# ProPrj_USB_Hub_Port_PCB_2026-06-10.net
KiCad netlist of a schematic drawn in EasyEDA Pro
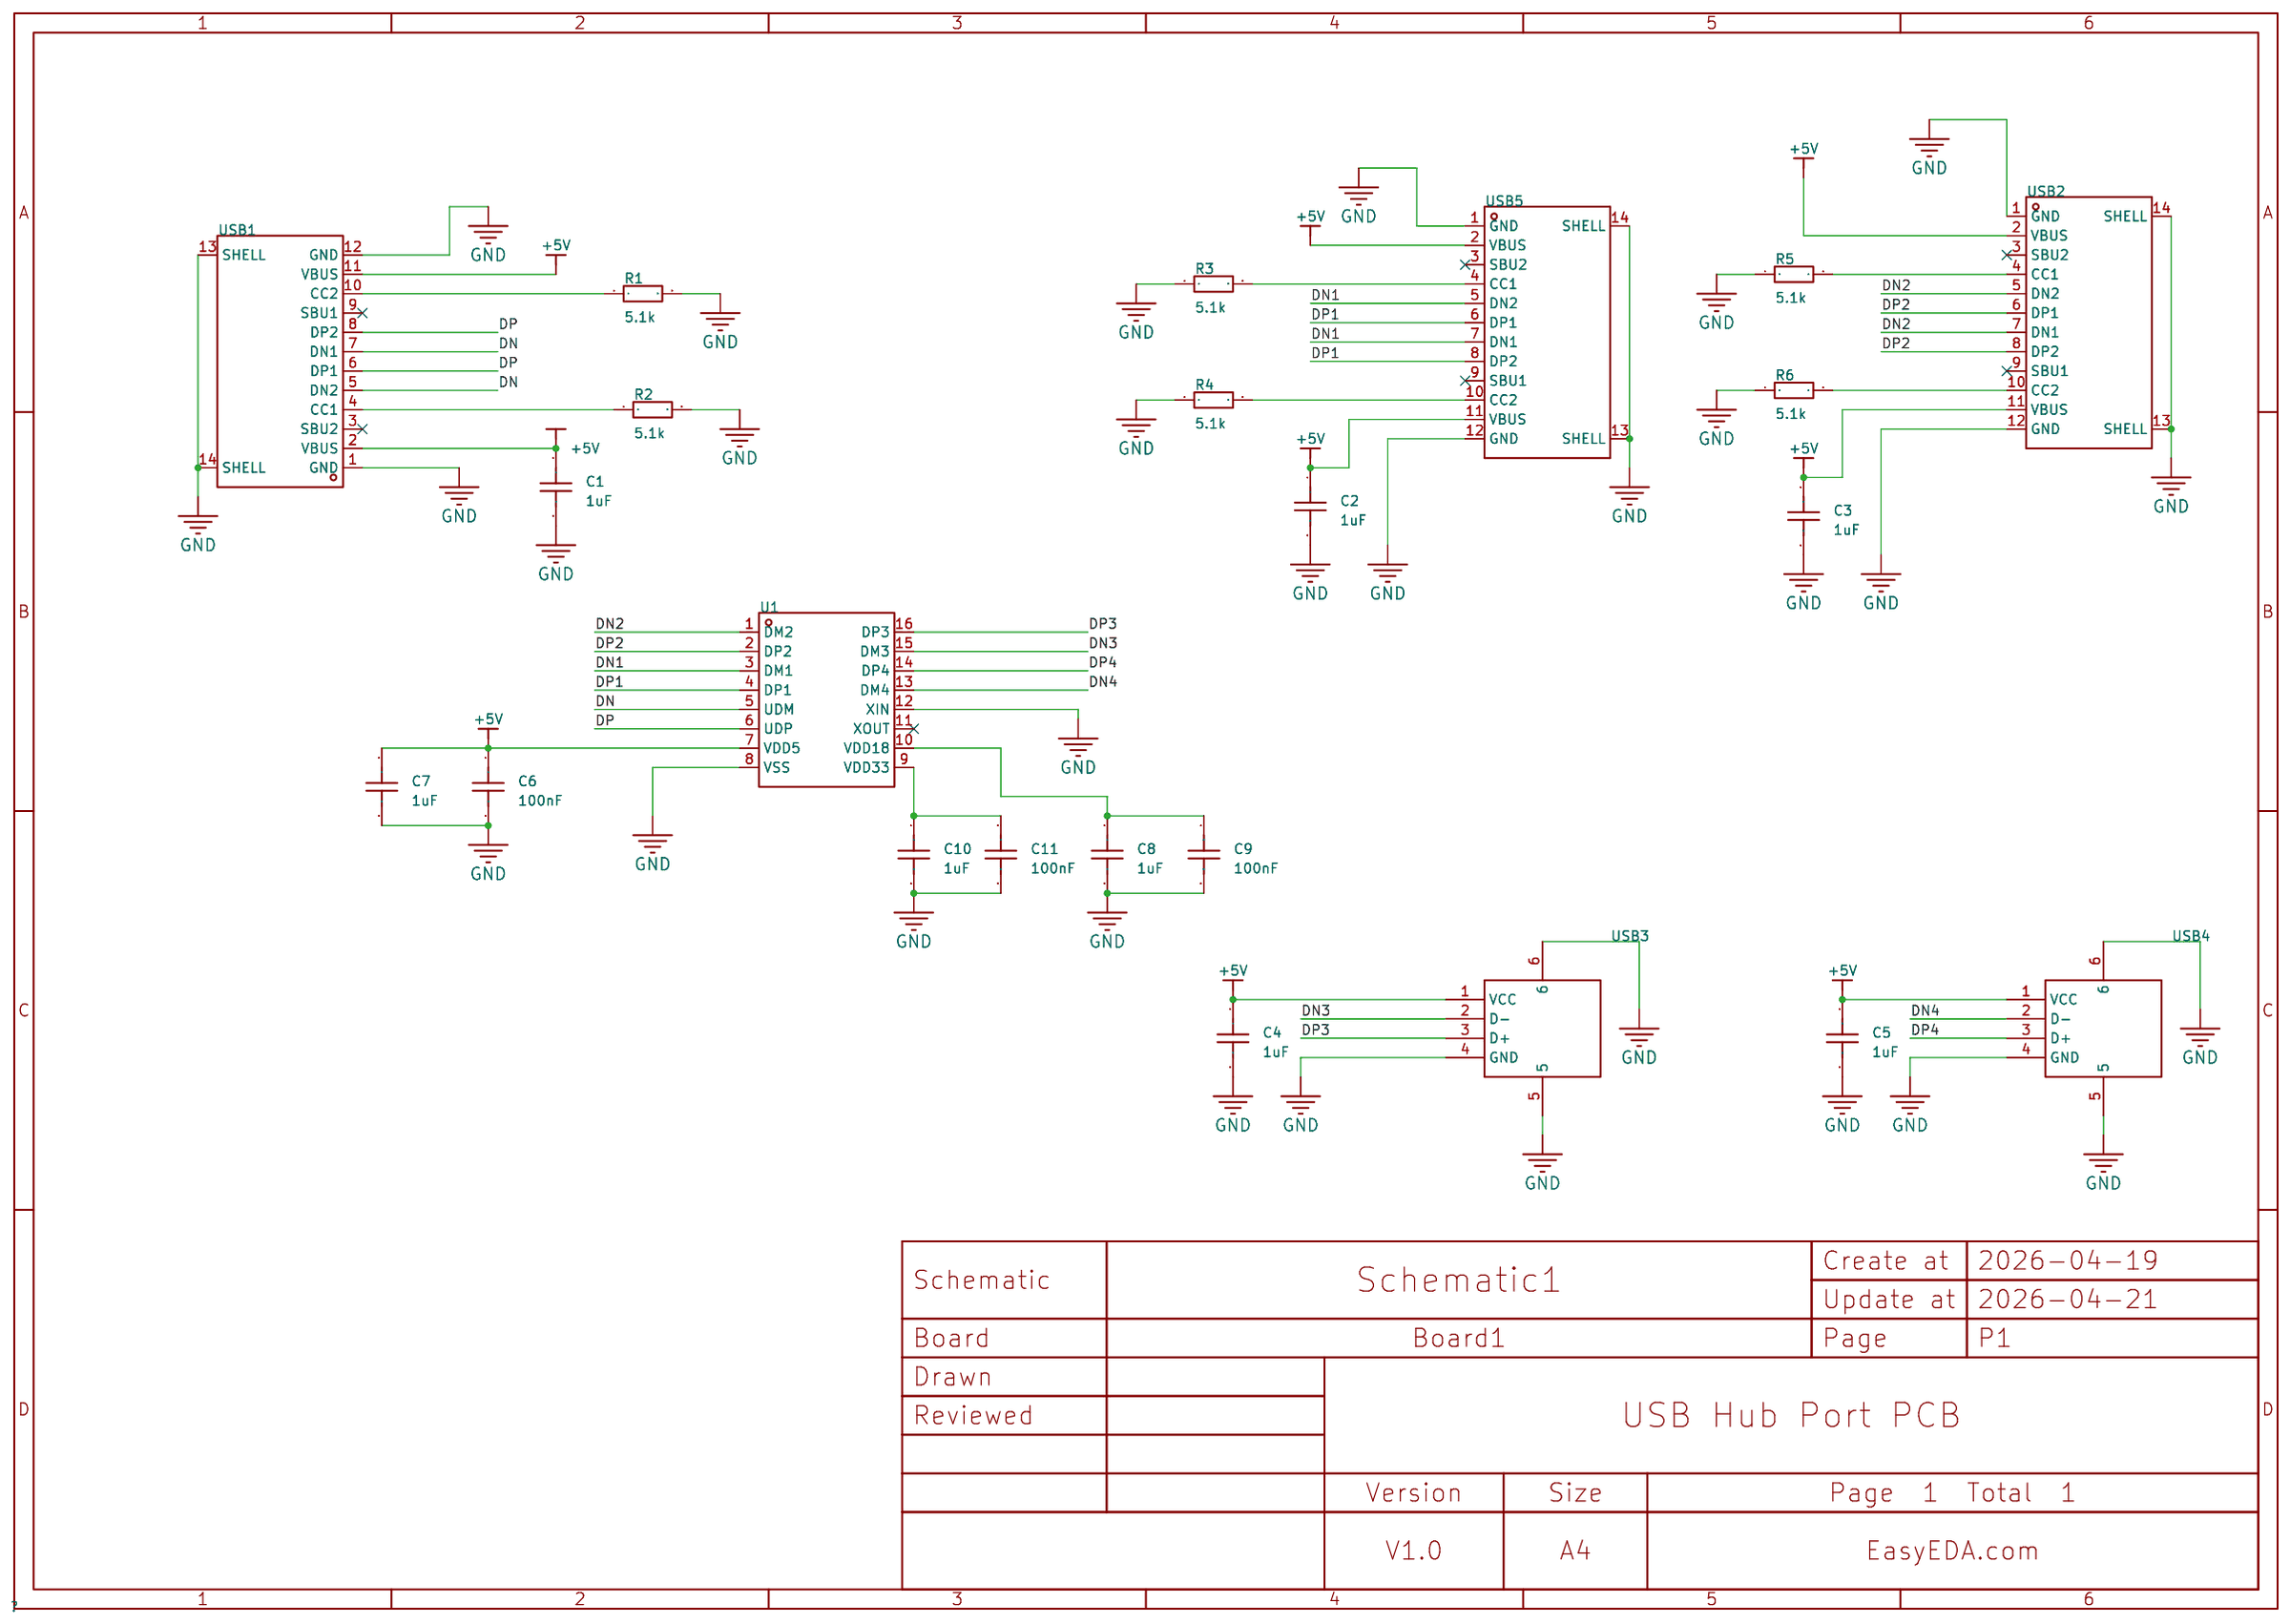
[diagram p0: schematic sheet]

(export (version "E")
  (design (tool "Eeschema 10.0.6"))
  (components
    (comp (ref "C1") (value "1uF") (footprint "easyedapro:C0603") (libsource (lib "easyedapro") (part "CAP")))
    (comp (ref "C2") (value "1uF") (footprint "easyedapro:C0603") (libsource (lib "easyedapro") (part "CAP")))
    (comp (ref "C3") (value "1uF") (footprint "easyedapro:C0603") (libsource (lib "easyedapro") (part "CAP")))
    (comp (ref "C4") (value "1uF") (footprint "easyedapro:C0603") (libsource (lib "easyedapro") (part "CAP")))
    (comp (ref "C5") (value "1uF") (footprint "easyedapro:C0603") (libsource (lib "easyedapro") (part "CAP")))
    (comp (ref "C6")
      (value "100nF")
      (footprint "easyedapro:C0603")
      (libsource (lib "easyedapro") (part "CAP"))
    )
    (comp (ref "C7") (value "1uF") (footprint "easyedapro:C0603") (libsource (lib "easyedapro") (part "CAP")))
    (comp (ref "C8") (value "1uF") (footprint "easyedapro:C0603") (libsource (lib "easyedapro") (part "CAP")))
    (comp (ref "C9")
      (value "100nF")
      (footprint "easyedapro:C0603")
      (libsource (lib "easyedapro") (part "CAP"))
    )
    (comp (ref "C10")
      (value "1uF")
      (footprint "easyedapro:C0603")
      (libsource (lib "easyedapro") (part "CAP"))
    )
    (comp (ref "C11")
      (value "100nF")
      (footprint "easyedapro:C0603")
      (libsource (lib "easyedapro") (part "CAP"))
    )
    (comp (ref "R1")
      (value "5.1k")
      (footprint "easyedapro:R0603")
      (libsource (lib "easyedapro") (part "Res"))
    )
    (comp (ref "R2")
      (value "5.1k")
      (footprint "easyedapro:R0603")
      (libsource (lib "easyedapro") (part "Res"))
    )
    (comp (ref "R3")
      (value "5.1k")
      (footprint "easyedapro:R0603")
      (libsource (lib "easyedapro") (part "Res"))
    )
    (comp (ref "R4")
      (value "5.1k")
      (footprint "easyedapro:R0603")
      (libsource (lib "easyedapro") (part "Res"))
    )
    (comp (ref "R5")
      (value "5.1k")
      (footprint "easyedapro:R0603")
      (libsource (lib "easyedapro") (part "Res"))
    )
    (comp (ref "R6")
      (value "5.1k")
      (footprint "easyedapro:R0603")
      (libsource (lib "easyedapro") (part "Res"))
    )
    (comp (ref "U1")
      (value "SL2.1s")
      (footprint "easyedapro:SSOP-16_L4.6-W2.6-P0.53-LS4.0-BL")
      (fields (field (name "Manufacturer") "CoreChips(和芯润德)"))
      (libsource (lib "easyedapro") (part "SL2.1S"))
    )
    (comp (ref "USB1")
      (value "TYPE-C 16PIN 2MD(073)")
      (footprint "easyedapro:USB-C-SMD_TYPE-C-6PIN-2MD-073")
      (fields (field (name "Manufacturer") "SHOU HAN(首韩)"))
      (libsource (lib "easyedapro") (part "TYPE-C 16PIN 2MD(073)"))
    )
    (comp (ref "USB2")
      (value "TYPE-C 16PIN 2MD(073)")
      (footprint "easyedapro:USB-C-SMD_TYPE-C-6PIN-2MD-073")
      (fields (field (name "Manufacturer") "SHOU HAN(首韩)"))
      (libsource (lib "easyedapro") (part "TYPE-C 16PIN 2MD(073)"))
    )
    (comp (ref "USB3")
      (value "10.0 QHHTZB6.3")
      (footprint "easyedapro:USB-A-TH_10.0QHHTZB6.3")
      (fields (field (name "Manufacturer") "SHOU HAN(首韩)"))
      (libsource (lib "easyedapro") (part "10.0 QHHTZB6.3"))
    )
    (comp (ref "USB4")
      (value "10.0 QHHTZB6.3")
      (footprint "easyedapro:USB-A-TH_10.0QHHTZB6.3")
      (fields (field (name "Manufacturer") "SHOU HAN(首韩)"))
      (libsource (lib "easyedapro") (part "10.0 QHHTZB6.3"))
    )
    (comp (ref "USB5")
      (value "TYPE-C 16PIN 2MD(073)")
      (footprint "easyedapro:USB-C-SMD_TYPE-C-6PIN-2MD-073")
      (fields (field (name "Manufacturer") "SHOU HAN(首韩)"))
      (libsource (lib "easyedapro") (part "TYPE-C 16PIN 2MD(073)"))
    )
  )
  (nets
    (net (code "1") (name "+5V") (class "Default")
      (node (ref "C1") (pin "1") (pinfunction "1_1") (pintype "input"))
      (node (ref "C2") (pin "1") (pinfunction "1_1") (pintype "input"))
      (node (ref "C3") (pin "1") (pinfunction "1_1") (pintype "input"))
      (node (ref "C4") (pin "1") (pinfunction "1_1") (pintype "input"))
      (node (ref "C5") (pin "1") (pinfunction "1_1") (pintype "input"))
      (node (ref "C6") (pin "1") (pinfunction "1_1") (pintype "input"))
      (node (ref "C7") (pin "1") (pinfunction "1_1") (pintype "input"))
      (node (ref "U1") (pin "7") (pinfunction "VDD5_7") (pintype "unspecified"))
      (node (ref "USB1") (pin "11") (pinfunction "VBUS_11") (pintype "unspecified"))
      (node (ref "USB1") (pin "2") (pinfunction "VBUS_2") (pintype "unspecified"))
      (node (ref "USB2") (pin "11") (pinfunction "VBUS_11") (pintype "unspecified"))
      (node (ref "USB2") (pin "2") (pinfunction "VBUS_2") (pintype "unspecified"))
      (node (ref "USB3") (pin "1") (pinfunction "VCC_1") (pintype "unspecified"))
      (node (ref "USB4") (pin "1") (pinfunction "VCC_1") (pintype "unspecified"))
      (node (ref "USB5") (pin "11") (pinfunction "VBUS_11") (pintype "unspecified"))
      (node (ref "USB5") (pin "2") (pinfunction "VBUS_2") (pintype "unspecified"))
    )
    (net (code "2") (name "/DN") (class "Default")
      (node (ref "U1") (pin "5") (pinfunction "UDM_5") (pintype "unspecified"))
      (node (ref "USB1") (pin "5") (pinfunction "DN2_5") (pintype "unspecified"))
      (node (ref "USB1") (pin "7") (pinfunction "DN1_7") (pintype "unspecified"))
    )
    (net (code "3") (name "/DN1") (class "Default")
      (node (ref "U1") (pin "3") (pinfunction "DM1_3") (pintype "unspecified"))
      (node (ref "USB5") (pin "5") (pinfunction "DN2_5") (pintype "unspecified"))
      (node (ref "USB5") (pin "7") (pinfunction "DN1_7") (pintype "unspecified"))
    )
    (net (code "4") (name "/DN2") (class "Default")
      (node (ref "U1") (pin "1") (pinfunction "DM2_1") (pintype "unspecified"))
      (node (ref "USB2") (pin "5") (pinfunction "DN2_5") (pintype "unspecified"))
      (node (ref "USB2") (pin "7") (pinfunction "DN1_7") (pintype "unspecified"))
    )
    (net (code "5") (name "/DN3") (class "Default")
      (node (ref "U1") (pin "15") (pinfunction "DM3_15") (pintype "unspecified"))
      (node (ref "USB3") (pin "2") (pinfunction "D-_2") (pintype "unspecified"))
    )
    (net (code "6") (name "/DN4") (class "Default")
      (node (ref "U1") (pin "13") (pinfunction "DM4_13") (pintype "unspecified"))
      (node (ref "USB4") (pin "2") (pinfunction "D-_2") (pintype "unspecified"))
    )
    (net (code "7") (name "/DP") (class "Default")
      (node (ref "U1") (pin "6") (pinfunction "UDP_6") (pintype "unspecified"))
      (node (ref "USB1") (pin "6") (pinfunction "DP1_6") (pintype "unspecified"))
      (node (ref "USB1") (pin "8") (pinfunction "DP2_8") (pintype "unspecified"))
    )
    (net (code "8") (name "/DP1") (class "Default")
      (node (ref "U1") (pin "4") (pinfunction "DP1_4") (pintype "unspecified"))
      (node (ref "USB5") (pin "6") (pinfunction "DP1_6") (pintype "unspecified"))
      (node (ref "USB5") (pin "8") (pinfunction "DP2_8") (pintype "unspecified"))
    )
    (net (code "9") (name "/DP2") (class "Default")
      (node (ref "U1") (pin "2") (pinfunction "DP2_2") (pintype "unspecified"))
      (node (ref "USB2") (pin "6") (pinfunction "DP1_6") (pintype "unspecified"))
      (node (ref "USB2") (pin "8") (pinfunction "DP2_8") (pintype "unspecified"))
    )
    (net (code "10") (name "/DP3") (class "Default")
      (node (ref "U1") (pin "16") (pinfunction "DP3_16") (pintype "unspecified"))
      (node (ref "USB3") (pin "3") (pinfunction "D+_3") (pintype "unspecified"))
    )
    (net (code "11") (name "/DP4") (class "Default")
      (node (ref "U1") (pin "14") (pinfunction "DP4_14") (pintype "unspecified"))
      (node (ref "USB4") (pin "3") (pinfunction "D+_3") (pintype "unspecified"))
    )
    (net (code "12") (name "GND") (class "Default")
      (node (ref "C1") (pin "2") (pinfunction "2_2") (pintype "input"))
      (node (ref "C10") (pin "2") (pinfunction "2_2") (pintype "input"))
      (node (ref "C11") (pin "2") (pinfunction "2_2") (pintype "input"))
      (node (ref "C2") (pin "2") (pinfunction "2_2") (pintype "input"))
      (node (ref "C3") (pin "2") (pinfunction "2_2") (pintype "input"))
      (node (ref "C4") (pin "2") (pinfunction "2_2") (pintype "input"))
      (node (ref "C5") (pin "2") (pinfunction "2_2") (pintype "input"))
      (node (ref "C6") (pin "2") (pinfunction "2_2") (pintype "input"))
      (node (ref "C7") (pin "2") (pinfunction "2_2") (pintype "input"))
      (node (ref "C8") (pin "2") (pinfunction "2_2") (pintype "input"))
      (node (ref "C9") (pin "2") (pinfunction "2_2") (pintype "input"))
      (node (ref "R1") (pin "2") (pinfunction "2_2") (pintype "input"))
      (node (ref "R2") (pin "2") (pinfunction "2_2") (pintype "input"))
      (node (ref "R3") (pin "1") (pinfunction "1_1") (pintype "input"))
      (node (ref "R4") (pin "1") (pinfunction "1_1") (pintype "input"))
      (node (ref "R5") (pin "1") (pinfunction "1_1") (pintype "input"))
      (node (ref "R6") (pin "1") (pinfunction "1_1") (pintype "input"))
      (node (ref "U1") (pin "12") (pinfunction "XIN_12") (pintype "unspecified"))
      (node (ref "U1") (pin "8") (pinfunction "VSS_8") (pintype "unspecified"))
      (node (ref "USB1") (pin "1") (pinfunction "GND_1") (pintype "unspecified"))
      (node (ref "USB1") (pin "12") (pinfunction "GND_12") (pintype "unspecified"))
      (node (ref "USB1") (pin "13") (pinfunction "SHELL_13") (pintype "unspecified"))
      (node (ref "USB1") (pin "14") (pinfunction "SHELL_14") (pintype "unspecified"))
      (node (ref "USB2") (pin "1") (pinfunction "GND_1") (pintype "unspecified"))
      (node (ref "USB2") (pin "12") (pinfunction "GND_12") (pintype "unspecified"))
      (node (ref "USB2") (pin "13") (pinfunction "SHELL_13") (pintype "unspecified"))
      (node (ref "USB2") (pin "14") (pinfunction "SHELL_14") (pintype "unspecified"))
      (node (ref "USB3") (pin "4") (pinfunction "GND_4") (pintype "unspecified"))
      (node (ref "USB3") (pin "5") (pinfunction "5_5") (pintype "unspecified"))
      (node (ref "USB3") (pin "6") (pinfunction "6_6") (pintype "unspecified"))
      (node (ref "USB4") (pin "4") (pinfunction "GND_4") (pintype "unspecified"))
      (node (ref "USB4") (pin "5") (pinfunction "5_5") (pintype "unspecified"))
      (node (ref "USB4") (pin "6") (pinfunction "6_6") (pintype "unspecified"))
      (node (ref "USB5") (pin "1") (pinfunction "GND_1") (pintype "unspecified"))
      (node (ref "USB5") (pin "12") (pinfunction "GND_12") (pintype "unspecified"))
      (node (ref "USB5") (pin "13") (pinfunction "SHELL_13") (pintype "unspecified"))
      (node (ref "USB5") (pin "14") (pinfunction "SHELL_14") (pintype "unspecified"))
    )
    (net (code "13") (name "Net-(U1-VDD18)") (class "Default")
      (node (ref "C8") (pin "1") (pinfunction "1_1") (pintype "input"))
      (node (ref "C9") (pin "1") (pinfunction "1_1") (pintype "input"))
      (node (ref "U1") (pin "10") (pinfunction "VDD18_10") (pintype "unspecified"))
    )
    (net (code "14") (name "Net-(U1-VDD33)") (class "Default")
      (node (ref "C10") (pin "1") (pinfunction "1_1") (pintype "input"))
      (node (ref "C11") (pin "1") (pinfunction "1_1") (pintype "input"))
      (node (ref "U1") (pin "9") (pinfunction "VDD33_9") (pintype "unspecified"))
    )
    (net (code "15") (name "Net-(USB1-CC1)") (class "Default")
      (node (ref "R2") (pin "1") (pinfunction "1_1") (pintype "input"))
      (node (ref "USB1") (pin "4") (pinfunction "CC1_4") (pintype "unspecified"))
    )
    (net (code "16") (name "Net-(USB1-CC2)") (class "Default")
      (node (ref "R1") (pin "1") (pinfunction "1_1") (pintype "input"))
      (node (ref "USB1") (pin "10") (pinfunction "CC2_10") (pintype "unspecified"))
    )
    (net (code "17") (name "Net-(USB2-CC1)") (class "Default")
      (node (ref "R5") (pin "2") (pinfunction "2_2") (pintype "input"))
      (node (ref "USB2") (pin "4") (pinfunction "CC1_4") (pintype "unspecified"))
    )
    (net (code "18") (name "Net-(USB2-CC2)") (class "Default")
      (node (ref "R6") (pin "2") (pinfunction "2_2") (pintype "input"))
      (node (ref "USB2") (pin "10") (pinfunction "CC2_10") (pintype "unspecified"))
    )
    (net (code "19") (name "Net-(USB5-CC1)") (class "Default")
      (node (ref "R3") (pin "2") (pinfunction "2_2") (pintype "input"))
      (node (ref "USB5") (pin "4") (pinfunction "CC1_4") (pintype "unspecified"))
    )
    (net (code "20") (name "Net-(USB5-CC2)") (class "Default")
      (node (ref "R4") (pin "2") (pinfunction "2_2") (pintype "input"))
      (node (ref "USB5") (pin "10") (pinfunction "CC2_10") (pintype "unspecified"))
    )
    (net (code "21") (name "unconnected-(U1-XOUT-Pad11)") (class "Default")
      (node (ref "U1") (pin "11") (pinfunction "XOUT_11") (pintype "unspecified+no_connect"))
    )
    (net (code "22") (name "unconnected-(USB1-SBU1-Pad9)") (class "Default")
      (node (ref "USB1") (pin "9") (pinfunction "SBU1_9") (pintype "unspecified+no_connect"))
    )
    (net (code "23") (name "unconnected-(USB1-SBU2-Pad3)") (class "Default")
      (node (ref "USB1") (pin "3") (pinfunction "SBU2_3") (pintype "unspecified+no_connect"))
    )
    (net (code "24") (name "unconnected-(USB2-SBU1-Pad9)") (class "Default")
      (node (ref "USB2") (pin "9") (pinfunction "SBU1_9") (pintype "unspecified+no_connect"))
    )
    (net (code "25") (name "unconnected-(USB2-SBU2-Pad3)") (class "Default")
      (node (ref "USB2") (pin "3") (pinfunction "SBU2_3") (pintype "unspecified+no_connect"))
    )
    (net (code "26") (name "unconnected-(USB5-SBU1-Pad9)") (class "Default")
      (node (ref "USB5") (pin "9") (pinfunction "SBU1_9") (pintype "unspecified+no_connect"))
    )
    (net (code "27") (name "unconnected-(USB5-SBU2-Pad3)") (class "Default")
      (node (ref "USB5") (pin "3") (pinfunction "SBU2_3") (pintype "unspecified+no_connect"))
    )
  )
)
